# IO.net
KiCad netlist of a schematic drawn in Altium Designer
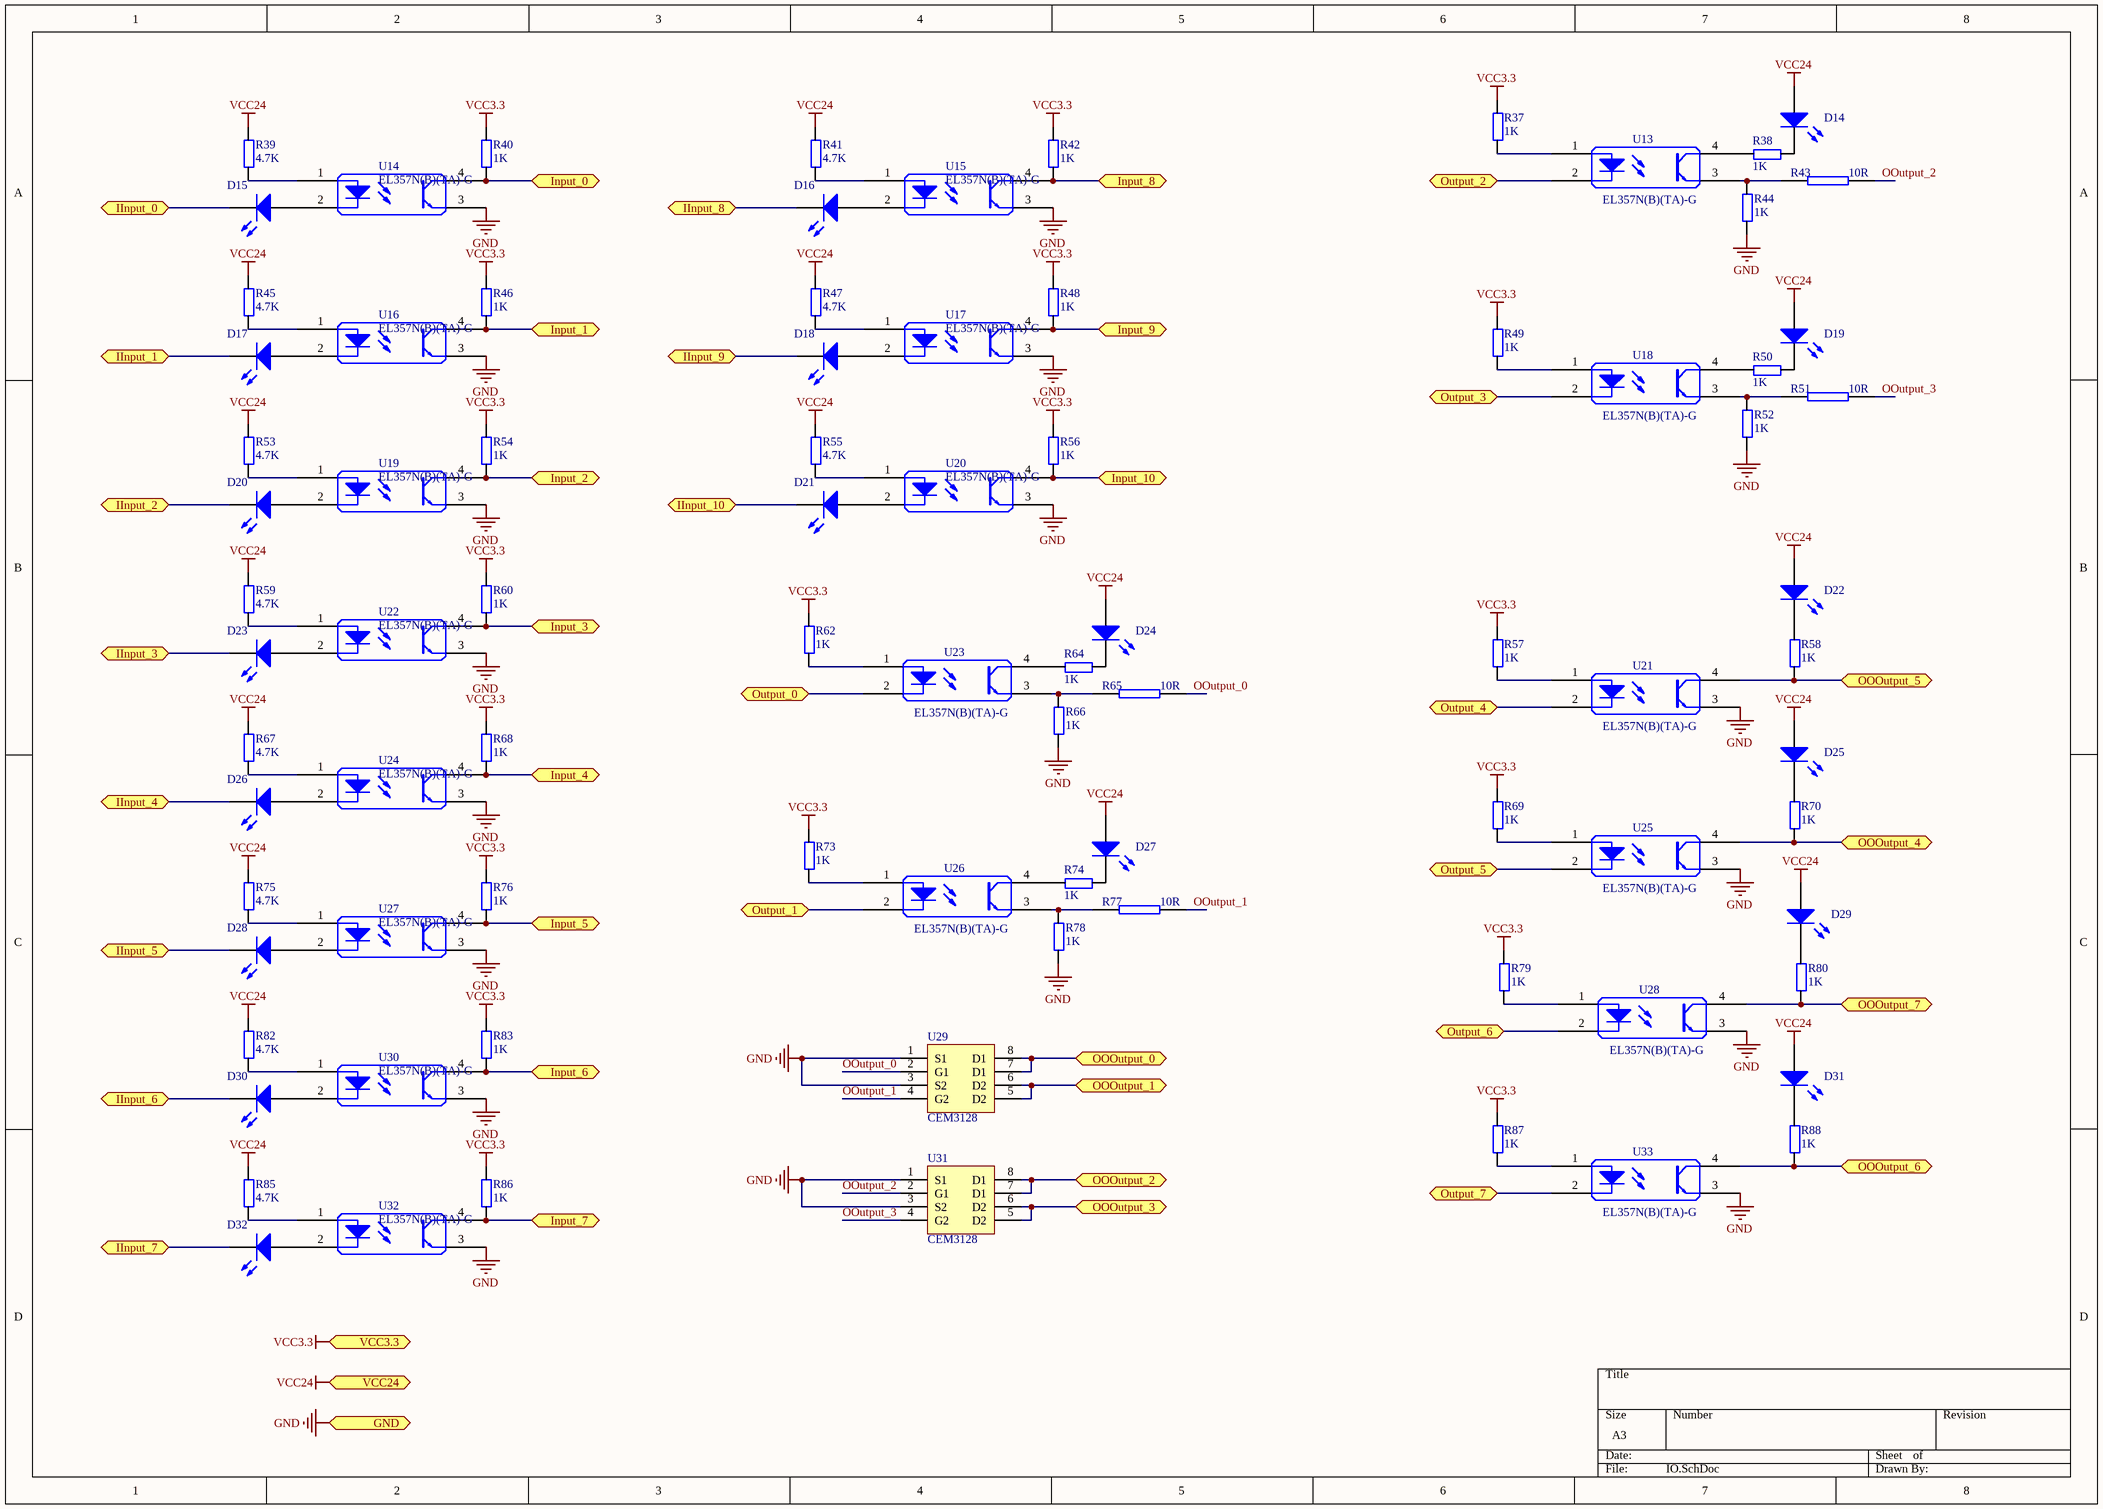
[diagram p0: IO.SchDoc]

(export (version "E")
  (design (tool "Eeschema 10.0.6"))
  (components
    (comp (ref "D14")
      (value "红灯 0805")
      (footprint "LC-0805_LED_S1")
      (description "Typical INFRARED GaAs LED")
      (fields (field (name "PUBLISHER") "Altium Limited"))
      (libsource (lib "继电器板_1") (part "LED0"))
    )
    (comp (ref "D15")
      (value "红灯 0805")
      (footprint "LC-0805_LED_S1")
      (description "Typical INFRARED GaAs LED")
      (fields (field (name "PUBLISHER") "Altium Limited"))
      (libsource (lib "继电器板_1") (part "LED0"))
    )
    (comp (ref "D16")
      (value "红灯 0805")
      (footprint "LC-0805_LED_S1")
      (description "Typical INFRARED GaAs LED")
      (fields (field (name "PUBLISHER") "Altium Limited"))
      (libsource (lib "继电器板_1") (part "LED0"))
    )
    (comp (ref "D17")
      (value "红灯 0805")
      (footprint "LC-0805_LED_S1")
      (description "Typical INFRARED GaAs LED")
      (fields (field (name "PUBLISHER") "Altium Limited"))
      (libsource (lib "继电器板_1") (part "LED0"))
    )
    (comp (ref "D18")
      (value "红灯 0805")
      (footprint "LC-0805_LED_S1")
      (description "Typical INFRARED GaAs LED")
      (fields (field (name "PUBLISHER") "Altium Limited"))
      (libsource (lib "继电器板_1") (part "LED0"))
    )
    (comp (ref "D19")
      (value "红灯 0805")
      (footprint "LC-0805_LED_S1")
      (description "Typical INFRARED GaAs LED")
      (fields (field (name "PUBLISHER") "Altium Limited"))
      (libsource (lib "继电器板_1") (part "LED0"))
    )
    (comp (ref "D20")
      (value "红灯 0805")
      (footprint "LC-0805_LED_S1")
      (description "Typical INFRARED GaAs LED")
      (fields (field (name "PUBLISHER") "Altium Limited"))
      (libsource (lib "继电器板_1") (part "LED0"))
    )
    (comp (ref "D21")
      (value "红灯 0805")
      (footprint "LC-0805_LED_S1")
      (description "Typical INFRARED GaAs LED")
      (fields (field (name "PUBLISHER") "Altium Limited"))
      (libsource (lib "继电器板_1") (part "LED0"))
    )
    (comp (ref "D22")
      (value "红灯 0805")
      (footprint "LC-0805_LED_S1")
      (description "Typical INFRARED GaAs LED")
      (fields (field (name "PUBLISHER") "Altium Limited"))
      (libsource (lib "继电器板_1") (part "LED0"))
    )
    (comp (ref "D23")
      (value "红灯 0805")
      (footprint "LC-0805_LED_S1")
      (description "Typical INFRARED GaAs LED")
      (fields (field (name "PUBLISHER") "Altium Limited"))
      (libsource (lib "继电器板_1") (part "LED0"))
    )
    (comp (ref "D24")
      (value "红灯 0805")
      (footprint "LC-0805_LED_S1")
      (description "Typical INFRARED GaAs LED")
      (fields (field (name "PUBLISHER") "Altium Limited"))
      (libsource (lib "继电器板_1") (part "LED0"))
    )
    (comp (ref "D25")
      (value "红灯 0805")
      (footprint "LC-0805_LED_S1")
      (description "Typical INFRARED GaAs LED")
      (fields (field (name "PUBLISHER") "Altium Limited"))
      (libsource (lib "继电器板_1") (part "LED0"))
    )
    (comp (ref "D26")
      (value "红灯 0805")
      (footprint "LC-0805_LED_S1")
      (description "Typical INFRARED GaAs LED")
      (fields (field (name "PUBLISHER") "Altium Limited"))
      (libsource (lib "继电器板_1") (part "LED0"))
    )
    (comp (ref "D27")
      (value "红灯 0805")
      (footprint "LC-0805_LED_S1")
      (description "Typical INFRARED GaAs LED")
      (fields (field (name "PUBLISHER") "Altium Limited"))
      (libsource (lib "继电器板_1") (part "LED0"))
    )
    (comp (ref "D28")
      (value "红灯 0805")
      (footprint "LC-0805_LED_S1")
      (description "Typical INFRARED GaAs LED")
      (fields (field (name "PUBLISHER") "Altium Limited"))
      (libsource (lib "继电器板_1") (part "LED0"))
    )
    (comp (ref "D29")
      (value "红灯 0805")
      (footprint "LC-0805_LED_S1")
      (description "Typical INFRARED GaAs LED")
      (fields (field (name "PUBLISHER") "Altium Limited"))
      (libsource (lib "继电器板_1") (part "LED0"))
    )
    (comp (ref "D30")
      (value "红灯 0805")
      (footprint "LC-0805_LED_S1")
      (description "Typical INFRARED GaAs LED")
      (fields (field (name "PUBLISHER") "Altium Limited"))
      (libsource (lib "继电器板_1") (part "LED0"))
    )
    (comp (ref "D31")
      (value "红灯 0805")
      (footprint "LC-0805_LED_S1")
      (description "Typical INFRARED GaAs LED")
      (fields (field (name "PUBLISHER") "Altium Limited"))
      (libsource (lib "继电器板_1") (part "LED0"))
    )
    (comp (ref "D32")
      (value "红灯 0805")
      (footprint "LC-0805_LED_S1")
      (description "Typical INFRARED GaAs LED")
      (fields (field (name "PUBLISHER") "Altium Limited"))
      (libsource (lib "继电器板_1") (part "LED0"))
    )
    (comp (ref "R37")
      (value "1K")
      (footprint "0603_R")
      (libsource (lib "Explorer STM32F407封装库") (part "R_2"))
    )
    (comp (ref "R38")
      (value "1K")
      (footprint "0603_R")
      (libsource (lib "Explorer STM32F407封装库") (part "R_2"))
    )
    (comp (ref "R39")
      (value "4.7K")
      (footprint "0603_R")
      (libsource (lib "Explorer STM32F407封装库") (part "R_2"))
    )
    (comp (ref "R40")
      (value "1K")
      (footprint "0603_R")
      (libsource (lib "Explorer STM32F407封装库") (part "R_2"))
    )
    (comp (ref "R41")
      (value "4.7K")
      (footprint "0603_R")
      (libsource (lib "Explorer STM32F407封装库") (part "R_2"))
    )
    (comp (ref "R42")
      (value "1K")
      (footprint "0603_R")
      (libsource (lib "Explorer STM32F407封装库") (part "R_2"))
    )
    (comp (ref "R43") (value "10R") (footprint "0603_R") (libsource (lib "*") (part "RES2")))
    (comp (ref "R44")
      (value "1K")
      (footprint "0603_R")
      (libsource (lib "Explorer STM32F407封装库") (part "R_2"))
    )
    (comp (ref "R45")
      (value "4.7K")
      (footprint "0603_R")
      (libsource (lib "Explorer STM32F407封装库") (part "R_2"))
    )
    (comp (ref "R46")
      (value "1K")
      (footprint "0603_R")
      (libsource (lib "Explorer STM32F407封装库") (part "R_2"))
    )
    (comp (ref "R47")
      (value "4.7K")
      (footprint "0603_R")
      (libsource (lib "Explorer STM32F407封装库") (part "R_2"))
    )
    (comp (ref "R48")
      (value "1K")
      (footprint "0603_R")
      (libsource (lib "Explorer STM32F407封装库") (part "R_2"))
    )
    (comp (ref "R49")
      (value "1K")
      (footprint "0603_R")
      (libsource (lib "Explorer STM32F407封装库") (part "R_2"))
    )
    (comp (ref "R50")
      (value "1K")
      (footprint "0603_R")
      (libsource (lib "Explorer STM32F407封装库") (part "R_2"))
    )
    (comp (ref "R51") (value "10R") (footprint "0603_R") (libsource (lib "*") (part "RES2")))
    (comp (ref "R52")
      (value "1K")
      (footprint "0603_R")
      (libsource (lib "Explorer STM32F407封装库") (part "R_2"))
    )
    (comp (ref "R53")
      (value "4.7K")
      (footprint "0603_R")
      (libsource (lib "Explorer STM32F407封装库") (part "R_2"))
    )
    (comp (ref "R54")
      (value "1K")
      (footprint "0603_R")
      (libsource (lib "Explorer STM32F407封装库") (part "R_2"))
    )
    (comp (ref "R55")
      (value "4.7K")
      (footprint "0603_R")
      (libsource (lib "Explorer STM32F407封装库") (part "R_2"))
    )
    (comp (ref "R56")
      (value "1K")
      (footprint "0603_R")
      (libsource (lib "Explorer STM32F407封装库") (part "R_2"))
    )
    (comp (ref "R57")
      (value "1K")
      (footprint "0603_R")
      (libsource (lib "Explorer STM32F407封装库") (part "R_2"))
    )
    (comp (ref "R58")
      (value "1K")
      (footprint "0603_R")
      (libsource (lib "Explorer STM32F407封装库") (part "R_2"))
    )
    (comp (ref "R59")
      (value "4.7K")
      (footprint "0603_R")
      (libsource (lib "Explorer STM32F407封装库") (part "R_2"))
    )
    (comp (ref "R60")
      (value "1K")
      (footprint "0603_R")
      (libsource (lib "Explorer STM32F407封装库") (part "R_2"))
    )
    (comp (ref "R62")
      (value "1K")
      (footprint "0603_R")
      (libsource (lib "Explorer STM32F407封装库") (part "R_2"))
    )
    (comp (ref "R64")
      (value "1K")
      (footprint "0603_R")
      (libsource (lib "Explorer STM32F407封装库") (part "R_2"))
    )
    (comp (ref "R65") (value "10R") (footprint "0603_R") (libsource (lib "*") (part "RES2")))
    (comp (ref "R66")
      (value "1K")
      (footprint "0603_R")
      (libsource (lib "Explorer STM32F407封装库") (part "R_2"))
    )
    (comp (ref "R67")
      (value "4.7K")
      (footprint "0603_R")
      (libsource (lib "Explorer STM32F407封装库") (part "R_2"))
    )
    (comp (ref "R68")
      (value "1K")
      (footprint "0603_R")
      (libsource (lib "Explorer STM32F407封装库") (part "R_2"))
    )
    (comp (ref "R69")
      (value "1K")
      (footprint "0603_R")
      (libsource (lib "Explorer STM32F407封装库") (part "R_2"))
    )
    (comp (ref "R70")
      (value "1K")
      (footprint "0603_R")
      (libsource (lib "Explorer STM32F407封装库") (part "R_2"))
    )
    (comp (ref "R73")
      (value "1K")
      (footprint "0603_R")
      (libsource (lib "Explorer STM32F407封装库") (part "R_2"))
    )
    (comp (ref "R74")
      (value "1K")
      (footprint "0603_R")
      (libsource (lib "Explorer STM32F407封装库") (part "R_2"))
    )
    (comp (ref "R75")
      (value "4.7K")
      (footprint "0603_R")
      (libsource (lib "Explorer STM32F407封装库") (part "R_2"))
    )
    (comp (ref "R76")
      (value "1K")
      (footprint "0603_R")
      (libsource (lib "Explorer STM32F407封装库") (part "R_2"))
    )
    (comp (ref "R77") (value "10R") (footprint "0603_R") (libsource (lib "*") (part "RES2")))
    (comp (ref "R78")
      (value "1K")
      (footprint "0603_R")
      (libsource (lib "Explorer STM32F407封装库") (part "R_2"))
    )
    (comp (ref "R79")
      (value "1K")
      (footprint "0603_R")
      (libsource (lib "Explorer STM32F407封装库") (part "R_2"))
    )
    (comp (ref "R80")
      (value "1K")
      (footprint "0603_R")
      (libsource (lib "Explorer STM32F407封装库") (part "R_2"))
    )
    (comp (ref "R82")
      (value "4.7K")
      (footprint "0603_R")
      (libsource (lib "Explorer STM32F407封装库") (part "R_2"))
    )
    (comp (ref "R83")
      (value "1K")
      (footprint "0603_R")
      (libsource (lib "Explorer STM32F407封装库") (part "R_2"))
    )
    (comp (ref "R85")
      (value "4.7K")
      (footprint "0603_R")
      (libsource (lib "Explorer STM32F407封装库") (part "R_2"))
    )
    (comp (ref "R86")
      (value "1K")
      (footprint "0603_R")
      (libsource (lib "Explorer STM32F407封装库") (part "R_2"))
    )
    (comp (ref "R87")
      (value "1K")
      (footprint "0603_R")
      (libsource (lib "Explorer STM32F407封装库") (part "R_2"))
    )
    (comp (ref "R88")
      (value "1K")
      (footprint "0603_R")
      (libsource (lib "Explorer STM32F407封装库") (part "R_2"))
    )
    (comp (ref "U13")
      (value "EL357N(B)(TA)-G")
      (footprint "LC-SOP-4_P2.54")
      (libsource (lib "*") (part "2701"))
    )
    (comp (ref "U14")
      (value "EL357N(B)(TA)-G")
      (footprint "LC-SOP-4_P2.54")
      (libsource (lib "*") (part "2701"))
    )
    (comp (ref "U15")
      (value "EL357N(B)(TA)-G")
      (footprint "LC-SOP-4_P2.54")
      (libsource (lib "*") (part "2701"))
    )
    (comp (ref "U16")
      (value "EL357N(B)(TA)-G")
      (footprint "LC-SOP-4_P2.54")
      (libsource (lib "*") (part "2701"))
    )
    (comp (ref "U17")
      (value "EL357N(B)(TA)-G")
      (footprint "LC-SOP-4_P2.54")
      (libsource (lib "*") (part "2701"))
    )
    (comp (ref "U18")
      (value "EL357N(B)(TA)-G")
      (footprint "LC-SOP-4_P2.54")
      (libsource (lib "*") (part "2701"))
    )
    (comp (ref "U19")
      (value "EL357N(B)(TA)-G")
      (footprint "LC-SOP-4_P2.54")
      (libsource (lib "*") (part "2701"))
    )
    (comp (ref "U20")
      (value "EL357N(B)(TA)-G")
      (footprint "LC-SOP-4_P2.54")
      (libsource (lib "*") (part "2701"))
    )
    (comp (ref "U21")
      (value "EL357N(B)(TA)-G")
      (footprint "LC-SOP-4_P2.54")
      (libsource (lib "*") (part "2701"))
    )
    (comp (ref "U22")
      (value "EL357N(B)(TA)-G")
      (footprint "LC-SOP-4_P2.54")
      (libsource (lib "*") (part "2701"))
    )
    (comp (ref "U23")
      (value "EL357N(B)(TA)-G")
      (footprint "LC-SOP-4_P2.54")
      (libsource (lib "*") (part "2701"))
    )
    (comp (ref "U24")
      (value "EL357N(B)(TA)-G")
      (footprint "LC-SOP-4_P2.54")
      (libsource (lib "*") (part "2701"))
    )
    (comp (ref "U25")
      (value "EL357N(B)(TA)-G")
      (footprint "LC-SOP-4_P2.54")
      (libsource (lib "*") (part "2701"))
    )
    (comp (ref "U26")
      (value "EL357N(B)(TA)-G")
      (footprint "LC-SOP-4_P2.54")
      (libsource (lib "*") (part "2701"))
    )
    (comp (ref "U27")
      (value "EL357N(B)(TA)-G")
      (footprint "LC-SOP-4_P2.54")
      (libsource (lib "*") (part "2701"))
    )
    (comp (ref "U28")
      (value "EL357N(B)(TA)-G")
      (footprint "LC-SOP-4_P2.54")
      (libsource (lib "*") (part "2701"))
    )
    (comp (ref "U29") (value "CEM3128") (footprint "SO-8") (libsource (lib "*") (part "AF4920N")))
    (comp (ref "U30")
      (value "EL357N(B)(TA)-G")
      (footprint "LC-SOP-4_P2.54")
      (libsource (lib "*") (part "2701"))
    )
    (comp (ref "U31") (value "CEM3128") (footprint "SO-8") (libsource (lib "*") (part "AF4920N")))
    (comp (ref "U32")
      (value "EL357N(B)(TA)-G")
      (footprint "LC-SOP-4_P2.54")
      (libsource (lib "*") (part "2701"))
    )
    (comp (ref "U33")
      (value "EL357N(B)(TA)-G")
      (footprint "LC-SOP-4_P2.54")
      (libsource (lib "*") (part "2701"))
    )
  )
  (nets
    (net (code "1") (name "/IInput_0") (class "Default")
      (node (ref "D15") (pin "K") (pinfunction "K_K") (pintype "passive"))
    )
    (net (code "2") (name "/IInput_1") (class "Default")
      (node (ref "D17") (pin "K") (pinfunction "K_K") (pintype "passive"))
    )
    (net (code "3") (name "/IInput_2") (class "Default")
      (node (ref "D20") (pin "K") (pinfunction "K_K") (pintype "passive"))
    )
    (net (code "4") (name "/IInput_3") (class "Default")
      (node (ref "D23") (pin "K") (pinfunction "K_K") (pintype "passive"))
    )
    (net (code "5") (name "/IInput_4") (class "Default")
      (node (ref "D26") (pin "K") (pinfunction "K_K") (pintype "passive"))
    )
    (net (code "6") (name "/IInput_5") (class "Default")
      (node (ref "D28") (pin "K") (pinfunction "K_K") (pintype "passive"))
    )
    (net (code "7") (name "/IInput_6") (class "Default")
      (node (ref "D30") (pin "K") (pinfunction "K_K") (pintype "passive"))
    )
    (net (code "8") (name "/IInput_7") (class "Default")
      (node (ref "D32") (pin "K") (pinfunction "K_K") (pintype "passive"))
    )
    (net (code "9") (name "/IInput_8") (class "Default")
      (node (ref "D16") (pin "K") (pinfunction "K_K") (pintype "passive"))
    )
    (net (code "10") (name "/IInput_9") (class "Default")
      (node (ref "D18") (pin "K") (pinfunction "K_K") (pintype "passive"))
    )
    (net (code "11") (name "/IInput_10") (class "Default")
      (node (ref "D21") (pin "K") (pinfunction "K_K") (pintype "passive"))
    )
    (net (code "12") (name "/Input_0") (class "Default")
      (node (ref "R40") (pin "1") (pintype "passive"))
      (node (ref "U14") (pin "4") (pintype "passive"))
    )
    (net (code "13") (name "/Input_1") (class "Default")
      (node (ref "R46") (pin "1") (pintype "passive"))
      (node (ref "U16") (pin "4") (pintype "passive"))
    )
    (net (code "14") (name "/Input_2") (class "Default")
      (node (ref "R54") (pin "1") (pintype "passive"))
      (node (ref "U19") (pin "4") (pintype "passive"))
    )
    (net (code "15") (name "/Input_3") (class "Default")
      (node (ref "R60") (pin "1") (pintype "passive"))
      (node (ref "U22") (pin "4") (pintype "passive"))
    )
    (net (code "16") (name "/Input_4") (class "Default")
      (node (ref "R68") (pin "1") (pintype "passive"))
      (node (ref "U24") (pin "4") (pintype "passive"))
    )
    (net (code "17") (name "/Input_5") (class "Default")
      (node (ref "R76") (pin "1") (pintype "passive"))
      (node (ref "U27") (pin "4") (pintype "passive"))
    )
    (net (code "18") (name "/Input_6") (class "Default")
      (node (ref "R83") (pin "1") (pintype "passive"))
      (node (ref "U30") (pin "4") (pintype "passive"))
    )
    (net (code "19") (name "/Input_7") (class "Default")
      (node (ref "R86") (pin "1") (pintype "passive"))
      (node (ref "U32") (pin "4") (pintype "passive"))
    )
    (net (code "20") (name "/Input_8") (class "Default")
      (node (ref "R42") (pin "1") (pintype "passive"))
      (node (ref "U15") (pin "4") (pintype "passive"))
    )
    (net (code "21") (name "/Input_9") (class "Default")
      (node (ref "R48") (pin "1") (pintype "passive"))
      (node (ref "U17") (pin "4") (pintype "passive"))
    )
    (net (code "22") (name "/Input_10") (class "Default")
      (node (ref "R56") (pin "1") (pintype "passive"))
      (node (ref "U20") (pin "4") (pintype "passive"))
    )
    (net (code "23") (name "/OOOutput_0") (class "Default")
      (node (ref "U29") (pin "7") (pinfunction "D1_7") (pintype "passive"))
      (node (ref "U29") (pin "8") (pinfunction "D1_8") (pintype "passive"))
    )
    (net (code "24") (name "/OOOutput_1") (class "Default")
      (node (ref "U29") (pin "5") (pinfunction "D2_5") (pintype "passive"))
      (node (ref "U29") (pin "6") (pinfunction "D2_6") (pintype "passive"))
    )
    (net (code "25") (name "/OOOutput_2") (class "Default")
      (node (ref "U31") (pin "7") (pinfunction "D1_7") (pintype "passive"))
      (node (ref "U31") (pin "8") (pinfunction "D1_8") (pintype "passive"))
    )
    (net (code "26") (name "/OOOutput_3") (class "Default")
      (node (ref "U31") (pin "5") (pinfunction "D2_5") (pintype "passive"))
      (node (ref "U31") (pin "6") (pinfunction "D2_6") (pintype "passive"))
    )
    (net (code "27") (name "/OOOutput_4") (class "Default")
      (node (ref "R70") (pin "1") (pintype "passive"))
      (node (ref "U25") (pin "4") (pintype "passive"))
    )
    (net (code "28") (name "/OOOutput_5") (class "Default")
      (node (ref "R58") (pin "1") (pintype "passive"))
      (node (ref "U21") (pin "4") (pintype "passive"))
    )
    (net (code "29") (name "/OOOutput_6") (class "Default")
      (node (ref "R88") (pin "1") (pintype "passive"))
      (node (ref "U33") (pin "4") (pintype "passive"))
    )
    (net (code "30") (name "/OOOutput_7") (class "Default")
      (node (ref "R80") (pin "1") (pintype "passive"))
      (node (ref "U28") (pin "4") (pintype "passive"))
    )
    (net (code "31") (name "/OOutput_0") (class "Default")
      (node (ref "R65") (pin "1") (pinfunction "1_1") (pintype "passive"))
      (node (ref "U29") (pin "2") (pinfunction "G1_2") (pintype "passive"))
    )
    (net (code "32") (name "/OOutput_1") (class "Default")
      (node (ref "R77") (pin "1") (pinfunction "1_1") (pintype "passive"))
      (node (ref "U29") (pin "4") (pinfunction "G2_4") (pintype "passive"))
    )
    (net (code "33") (name "/OOutput_2") (class "Default")
      (node (ref "R43") (pin "1") (pinfunction "1_1") (pintype "passive"))
      (node (ref "U31") (pin "2") (pinfunction "G1_2") (pintype "passive"))
    )
    (net (code "34") (name "/OOutput_3") (class "Default")
      (node (ref "R51") (pin "1") (pinfunction "1_1") (pintype "passive"))
      (node (ref "U31") (pin "4") (pinfunction "G2_4") (pintype "passive"))
    )
    (net (code "35") (name "/Output_0") (class "Default") (node (ref "U23") (pin "2") (pintype "passive")))
    (net (code "36") (name "/Output_1") (class "Default") (node (ref "U26") (pin "2") (pintype "passive")))
    (net (code "37") (name "/Output_2") (class "Default") (node (ref "U13") (pin "2") (pintype "passive")))
    (net (code "38") (name "/Output_3") (class "Default") (node (ref "U18") (pin "2") (pintype "passive")))
    (net (code "39") (name "/Output_4") (class "Default") (node (ref "U21") (pin "2") (pintype "passive")))
    (net (code "40") (name "/Output_5") (class "Default") (node (ref "U25") (pin "2") (pintype "passive")))
    (net (code "41") (name "/Output_6") (class "Default") (node (ref "U28") (pin "2") (pintype "passive")))
    (net (code "42") (name "/Output_7") (class "Default") (node (ref "U33") (pin "2") (pintype "passive")))
    (net (code "43") (name "GND") (class "Default")
      (node (ref "R44") (pin "1") (pintype "passive"))
      (node (ref "R52") (pin "1") (pintype "passive"))
      (node (ref "R66") (pin "1") (pintype "passive"))
      (node (ref "R78") (pin "1") (pintype "passive"))
      (node (ref "U14") (pin "3") (pintype "passive"))
      (node (ref "U15") (pin "3") (pintype "passive"))
      (node (ref "U16") (pin "3") (pintype "passive"))
      (node (ref "U17") (pin "3") (pintype "passive"))
      (node (ref "U19") (pin "3") (pintype "passive"))
      (node (ref "U20") (pin "3") (pintype "passive"))
      (node (ref "U21") (pin "3") (pintype "passive"))
      (node (ref "U22") (pin "3") (pintype "passive"))
      (node (ref "U24") (pin "3") (pintype "passive"))
      (node (ref "U25") (pin "3") (pintype "passive"))
      (node (ref "U27") (pin "3") (pintype "passive"))
      (node (ref "U28") (pin "3") (pintype "passive"))
      (node (ref "U29") (pin "1") (pinfunction "S1_1") (pintype "passive"))
      (node (ref "U29") (pin "3") (pinfunction "S2_3") (pintype "passive"))
      (node (ref "U30") (pin "3") (pintype "passive"))
      (node (ref "U31") (pin "1") (pinfunction "S1_1") (pintype "passive"))
      (node (ref "U31") (pin "3") (pinfunction "S2_3") (pintype "passive"))
      (node (ref "U32") (pin "3") (pintype "passive"))
      (node (ref "U33") (pin "3") (pintype "passive"))
    )
    (net (code "44") (name "Net-(D14-PadK)") (class "Default")
      (node (ref "D14") (pin "K") (pinfunction "K_K") (pintype "passive"))
      (node (ref "R38") (pin "2") (pintype "passive"))
    )
    (net (code "45") (name "Net-(D15-PadA)") (class "Default")
      (node (ref "D15") (pin "A") (pinfunction "A_A") (pintype "passive"))
      (node (ref "U14") (pin "2") (pintype "passive"))
    )
    (net (code "46") (name "Net-(D16-PadA)") (class "Default")
      (node (ref "D16") (pin "A") (pinfunction "A_A") (pintype "passive"))
      (node (ref "U15") (pin "2") (pintype "passive"))
    )
    (net (code "47") (name "Net-(D17-PadA)") (class "Default")
      (node (ref "D17") (pin "A") (pinfunction "A_A") (pintype "passive"))
      (node (ref "U16") (pin "2") (pintype "passive"))
    )
    (net (code "48") (name "Net-(D18-PadA)") (class "Default")
      (node (ref "D18") (pin "A") (pinfunction "A_A") (pintype "passive"))
      (node (ref "U17") (pin "2") (pintype "passive"))
    )
    (net (code "49") (name "Net-(D19-PadK)") (class "Default")
      (node (ref "D19") (pin "K") (pinfunction "K_K") (pintype "passive"))
      (node (ref "R50") (pin "2") (pintype "passive"))
    )
    (net (code "50") (name "Net-(D20-PadA)") (class "Default")
      (node (ref "D20") (pin "A") (pinfunction "A_A") (pintype "passive"))
      (node (ref "U19") (pin "2") (pintype "passive"))
    )
    (net (code "51") (name "Net-(D21-PadA)") (class "Default")
      (node (ref "D21") (pin "A") (pinfunction "A_A") (pintype "passive"))
      (node (ref "U20") (pin "2") (pintype "passive"))
    )
    (net (code "52") (name "Net-(D22-PadK)") (class "Default")
      (node (ref "D22") (pin "K") (pinfunction "K_K") (pintype "passive"))
      (node (ref "R58") (pin "2") (pintype "passive"))
    )
    (net (code "53") (name "Net-(D23-PadA)") (class "Default")
      (node (ref "D23") (pin "A") (pinfunction "A_A") (pintype "passive"))
      (node (ref "U22") (pin "2") (pintype "passive"))
    )
    (net (code "54") (name "Net-(D24-PadK)") (class "Default")
      (node (ref "D24") (pin "K") (pinfunction "K_K") (pintype "passive"))
      (node (ref "R64") (pin "2") (pintype "passive"))
    )
    (net (code "55") (name "Net-(D25-PadK)") (class "Default")
      (node (ref "D25") (pin "K") (pinfunction "K_K") (pintype "passive"))
      (node (ref "R70") (pin "2") (pintype "passive"))
    )
    (net (code "56") (name "Net-(D26-PadA)") (class "Default")
      (node (ref "D26") (pin "A") (pinfunction "A_A") (pintype "passive"))
      (node (ref "U24") (pin "2") (pintype "passive"))
    )
    (net (code "57") (name "Net-(D27-PadK)") (class "Default")
      (node (ref "D27") (pin "K") (pinfunction "K_K") (pintype "passive"))
      (node (ref "R74") (pin "2") (pintype "passive"))
    )
    (net (code "58") (name "Net-(D28-PadA)") (class "Default")
      (node (ref "D28") (pin "A") (pinfunction "A_A") (pintype "passive"))
      (node (ref "U27") (pin "2") (pintype "passive"))
    )
    (net (code "59") (name "Net-(D29-PadK)") (class "Default")
      (node (ref "D29") (pin "K") (pinfunction "K_K") (pintype "passive"))
      (node (ref "R80") (pin "2") (pintype "passive"))
    )
    (net (code "60") (name "Net-(D30-PadA)") (class "Default")
      (node (ref "D30") (pin "A") (pinfunction "A_A") (pintype "passive"))
      (node (ref "U30") (pin "2") (pintype "passive"))
    )
    (net (code "61") (name "Net-(D31-PadK)") (class "Default")
      (node (ref "D31") (pin "K") (pinfunction "K_K") (pintype "passive"))
      (node (ref "R88") (pin "2") (pintype "passive"))
    )
    (net (code "62") (name "Net-(D32-PadA)") (class "Default")
      (node (ref "D32") (pin "A") (pinfunction "A_A") (pintype "passive"))
      (node (ref "U32") (pin "2") (pintype "passive"))
    )
    (net (code "63") (name "Net-(R37-Pad1)") (class "Default")
      (node (ref "R37") (pin "1") (pintype "passive"))
      (node (ref "U13") (pin "1") (pintype "passive"))
    )
    (net (code "64") (name "Net-(R38-Pad1)") (class "Default")
      (node (ref "R38") (pin "1") (pintype "passive"))
      (node (ref "U13") (pin "4") (pintype "passive"))
    )
    (net (code "65") (name "Net-(R39-Pad1)") (class "Default")
      (node (ref "R39") (pin "1") (pintype "passive"))
      (node (ref "U14") (pin "1") (pintype "passive"))
    )
    (net (code "66") (name "Net-(R41-Pad1)") (class "Default")
      (node (ref "R41") (pin "1") (pintype "passive"))
      (node (ref "U15") (pin "1") (pintype "passive"))
    )
    (net (code "67") (name "Net-(R43-Pad2)") (class "Default")
      (node (ref "R43") (pin "2") (pinfunction "2_2") (pintype "passive"))
      (node (ref "R44") (pin "2") (pintype "passive"))
      (node (ref "U13") (pin "3") (pintype "passive"))
    )
    (net (code "68") (name "Net-(R45-Pad1)") (class "Default")
      (node (ref "R45") (pin "1") (pintype "passive"))
      (node (ref "U16") (pin "1") (pintype "passive"))
    )
    (net (code "69") (name "Net-(R47-Pad1)") (class "Default")
      (node (ref "R47") (pin "1") (pintype "passive"))
      (node (ref "U17") (pin "1") (pintype "passive"))
    )
    (net (code "70") (name "Net-(R49-Pad1)") (class "Default")
      (node (ref "R49") (pin "1") (pintype "passive"))
      (node (ref "U18") (pin "1") (pintype "passive"))
    )
    (net (code "71") (name "Net-(R50-Pad1)") (class "Default")
      (node (ref "R50") (pin "1") (pintype "passive"))
      (node (ref "U18") (pin "4") (pintype "passive"))
    )
    (net (code "72") (name "Net-(R51-Pad2)") (class "Default")
      (node (ref "R51") (pin "2") (pinfunction "2_2") (pintype "passive"))
      (node (ref "R52") (pin "2") (pintype "passive"))
      (node (ref "U18") (pin "3") (pintype "passive"))
    )
    (net (code "73") (name "Net-(R53-Pad1)") (class "Default")
      (node (ref "R53") (pin "1") (pintype "passive"))
      (node (ref "U19") (pin "1") (pintype "passive"))
    )
    (net (code "74") (name "Net-(R55-Pad1)") (class "Default")
      (node (ref "R55") (pin "1") (pintype "passive"))
      (node (ref "U20") (pin "1") (pintype "passive"))
    )
    (net (code "75") (name "Net-(R57-Pad1)") (class "Default")
      (node (ref "R57") (pin "1") (pintype "passive"))
      (node (ref "U21") (pin "1") (pintype "passive"))
    )
    (net (code "76") (name "Net-(R59-Pad1)") (class "Default")
      (node (ref "R59") (pin "1") (pintype "passive"))
      (node (ref "U22") (pin "1") (pintype "passive"))
    )
    (net (code "77") (name "Net-(R62-Pad1)") (class "Default")
      (node (ref "R62") (pin "1") (pintype "passive"))
      (node (ref "U23") (pin "1") (pintype "passive"))
    )
    (net (code "78") (name "Net-(R64-Pad1)") (class "Default")
      (node (ref "R64") (pin "1") (pintype "passive"))
      (node (ref "U23") (pin "4") (pintype "passive"))
    )
    (net (code "79") (name "Net-(R65-Pad2)") (class "Default")
      (node (ref "R65") (pin "2") (pinfunction "2_2") (pintype "passive"))
      (node (ref "R66") (pin "2") (pintype "passive"))
      (node (ref "U23") (pin "3") (pintype "passive"))
    )
    (net (code "80") (name "Net-(R67-Pad1)") (class "Default")
      (node (ref "R67") (pin "1") (pintype "passive"))
      (node (ref "U24") (pin "1") (pintype "passive"))
    )
    (net (code "81") (name "Net-(R69-Pad1)") (class "Default")
      (node (ref "R69") (pin "1") (pintype "passive"))
      (node (ref "U25") (pin "1") (pintype "passive"))
    )
    (net (code "82") (name "Net-(R73-Pad1)") (class "Default")
      (node (ref "R73") (pin "1") (pintype "passive"))
      (node (ref "U26") (pin "1") (pintype "passive"))
    )
    (net (code "83") (name "Net-(R74-Pad1)") (class "Default")
      (node (ref "R74") (pin "1") (pintype "passive"))
      (node (ref "U26") (pin "4") (pintype "passive"))
    )
    (net (code "84") (name "Net-(R75-Pad1)") (class "Default")
      (node (ref "R75") (pin "1") (pintype "passive"))
      (node (ref "U27") (pin "1") (pintype "passive"))
    )
    (net (code "85") (name "Net-(R77-Pad2)") (class "Default")
      (node (ref "R77") (pin "2") (pinfunction "2_2") (pintype "passive"))
      (node (ref "R78") (pin "2") (pintype "passive"))
      (node (ref "U26") (pin "3") (pintype "passive"))
    )
    (net (code "86") (name "Net-(R79-Pad1)") (class "Default")
      (node (ref "R79") (pin "1") (pintype "passive"))
      (node (ref "U28") (pin "1") (pintype "passive"))
    )
    (net (code "87") (name "Net-(R82-Pad1)") (class "Default")
      (node (ref "R82") (pin "1") (pintype "passive"))
      (node (ref "U30") (pin "1") (pintype "passive"))
    )
    (net (code "88") (name "Net-(R85-Pad1)") (class "Default")
      (node (ref "R85") (pin "1") (pintype "passive"))
      (node (ref "U32") (pin "1") (pintype "passive"))
    )
    (net (code "89") (name "Net-(R87-Pad1)") (class "Default")
      (node (ref "R87") (pin "1") (pintype "passive"))
      (node (ref "U33") (pin "1") (pintype "passive"))
    )
    (net (code "90") (name "VCC3.3") (class "Default")
      (node (ref "R37") (pin "2") (pintype "passive"))
      (node (ref "R40") (pin "2") (pintype "passive"))
      (node (ref "R42") (pin "2") (pintype "passive"))
      (node (ref "R46") (pin "2") (pintype "passive"))
      (node (ref "R48") (pin "2") (pintype "passive"))
      (node (ref "R49") (pin "2") (pintype "passive"))
      (node (ref "R54") (pin "2") (pintype "passive"))
      (node (ref "R56") (pin "2") (pintype "passive"))
      (node (ref "R57") (pin "2") (pintype "passive"))
      (node (ref "R60") (pin "2") (pintype "passive"))
      (node (ref "R62") (pin "2") (pintype "passive"))
      (node (ref "R68") (pin "2") (pintype "passive"))
      (node (ref "R69") (pin "2") (pintype "passive"))
      (node (ref "R73") (pin "2") (pintype "passive"))
      (node (ref "R76") (pin "2") (pintype "passive"))
      (node (ref "R79") (pin "2") (pintype "passive"))
      (node (ref "R83") (pin "2") (pintype "passive"))
      (node (ref "R86") (pin "2") (pintype "passive"))
      (node (ref "R87") (pin "2") (pintype "passive"))
    )
    (net (code "91") (name "VCC24") (class "Default")
      (node (ref "D14") (pin "A") (pinfunction "A_A") (pintype "passive"))
      (node (ref "D19") (pin "A") (pinfunction "A_A") (pintype "passive"))
      (node (ref "D22") (pin "A") (pinfunction "A_A") (pintype "passive"))
      (node (ref "D24") (pin "A") (pinfunction "A_A") (pintype "passive"))
      (node (ref "D25") (pin "A") (pinfunction "A_A") (pintype "passive"))
      (node (ref "D27") (pin "A") (pinfunction "A_A") (pintype "passive"))
      (node (ref "D29") (pin "A") (pinfunction "A_A") (pintype "passive"))
      (node (ref "D31") (pin "A") (pinfunction "A_A") (pintype "passive"))
      (node (ref "R39") (pin "2") (pintype "passive"))
      (node (ref "R41") (pin "2") (pintype "passive"))
      (node (ref "R45") (pin "2") (pintype "passive"))
      (node (ref "R47") (pin "2") (pintype "passive"))
      (node (ref "R53") (pin "2") (pintype "passive"))
      (node (ref "R55") (pin "2") (pintype "passive"))
      (node (ref "R59") (pin "2") (pintype "passive"))
      (node (ref "R67") (pin "2") (pintype "passive"))
      (node (ref "R75") (pin "2") (pintype "passive"))
      (node (ref "R82") (pin "2") (pintype "passive"))
      (node (ref "R85") (pin "2") (pintype "passive"))
    )
  )
)
